# BabyPC.net
KiCad netlist of a schematic drawn in EAGLE
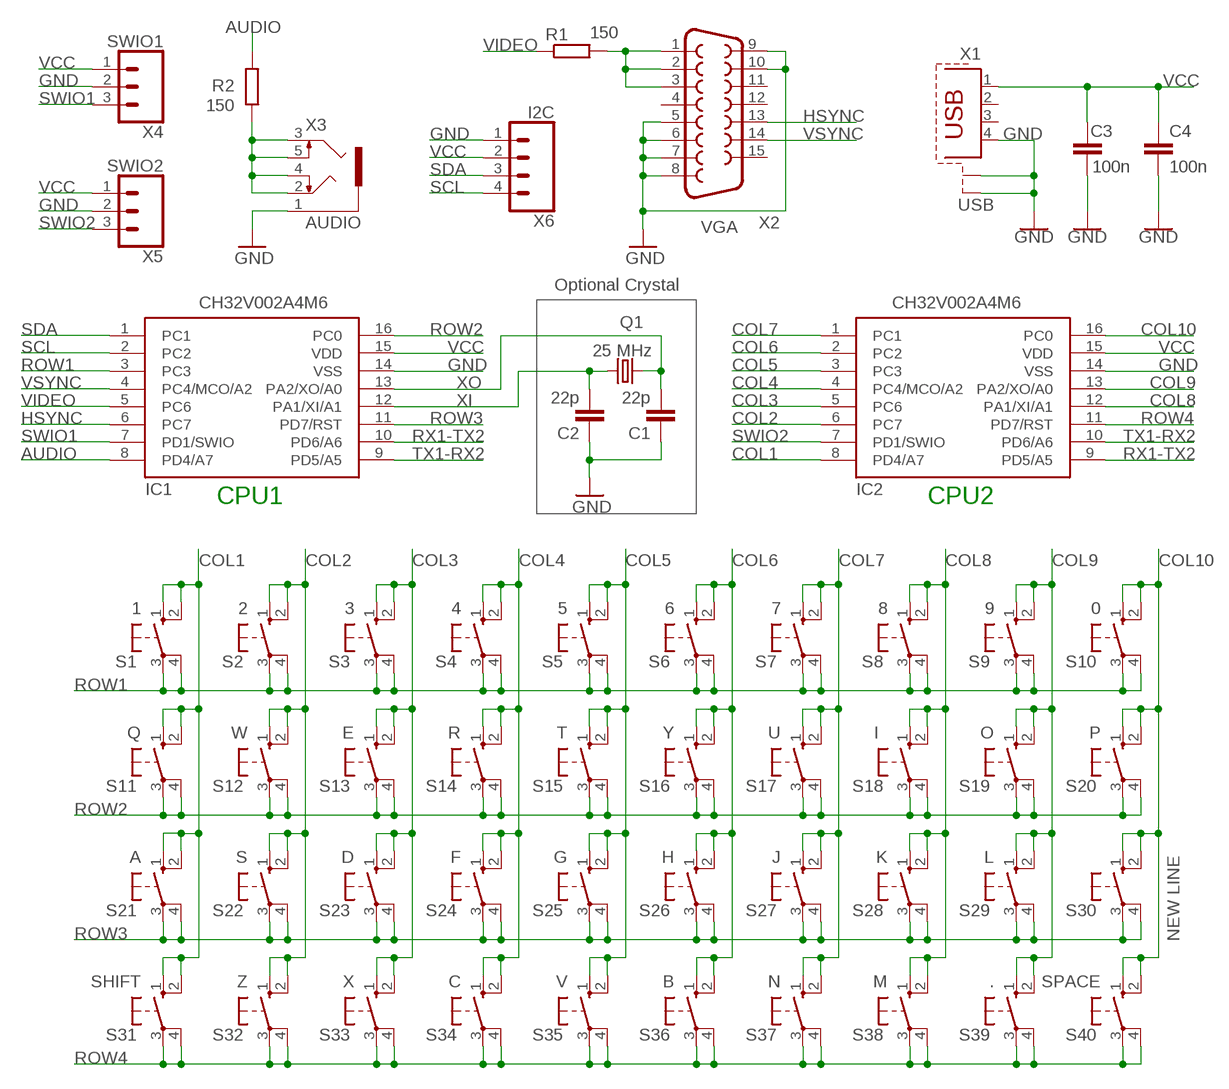
[diagram p0: schematic, sheet 1]

(export (version "E")
  (design (tool "Eeschema 10.0.6"))
  (components
    (comp (ref "C1")
      (value "22p")
      (footprint "eagle-import:C050-024X044")
      (libsource (lib "eagle-import") (part "C-EU050-024X044"))
    )
    (comp (ref "C2")
      (value "22p")
      (footprint "eagle-import:C050-024X044")
      (libsource (lib "eagle-import") (part "C-EU050-024X044"))
    )
    (comp (ref "C3")
      (value "100n")
      (footprint "eagle-import:C050-024X044")
      (libsource (lib "eagle-import") (part "C-EU050-024X044"))
    )
    (comp (ref "C4")
      (value "100n")
      (footprint "eagle-import:C050-024X044")
      (libsource (lib "eagle-import") (part "C-EU050-024X044"))
    )
    (comp (ref "IC1")
      (value "CH32V002A4M6")
      (footprint "eagle-import:SOP16")
      (libsource (lib "eagle-import") (part "CH32V002A4M6"))
    )
    (comp (ref "IC2")
      (value "CH32V002A4M6")
      (footprint "eagle-import:SOP16")
      (libsource (lib "eagle-import") (part "CH32V002A4M6"))
    )
    (comp (ref "Q1")
      (value "25 MHz")
      (footprint "eagle-import:HC49U-V")
      (libsource (lib "eagle-import") (part "CRYSTALHC49U-V"))
    )
    (comp (ref "R1")
      (value "150")
      (footprint "eagle-import:0204_7")
      (libsource (lib "eagle-import") (part "R-EU_0204/7"))
    )
    (comp (ref "R2")
      (value "150")
      (footprint "eagle-import:0204_7")
      (libsource (lib "eagle-import") (part "R-EU_0204/7"))
    )
    (comp (ref "S1")
      (value "1")
      (footprint "eagle-import:B3F-10XX")
      (fields (field (name "MPN") "B3F-1000"))
      (libsource (lib "eagle-import") (part "10-XX"))
    )
    (comp (ref "S2")
      (value "2")
      (footprint "eagle-import:B3F-10XX")
      (fields (field (name "MPN") "B3F-1000"))
      (libsource (lib "eagle-import") (part "10-XX"))
    )
    (comp (ref "S3")
      (value "3")
      (footprint "eagle-import:B3F-10XX")
      (fields (field (name "MPN") "B3F-1000"))
      (libsource (lib "eagle-import") (part "10-XX"))
    )
    (comp (ref "S4")
      (value "4")
      (footprint "eagle-import:B3F-10XX")
      (fields (field (name "MPN") "B3F-1000"))
      (libsource (lib "eagle-import") (part "10-XX"))
    )
    (comp (ref "S5")
      (value "5")
      (footprint "eagle-import:B3F-10XX")
      (fields (field (name "MPN") "B3F-1000"))
      (libsource (lib "eagle-import") (part "10-XX"))
    )
    (comp (ref "S6")
      (value "6")
      (footprint "eagle-import:B3F-10XX")
      (fields (field (name "MPN") "B3F-1000"))
      (libsource (lib "eagle-import") (part "10-XX"))
    )
    (comp (ref "S7")
      (value "7")
      (footprint "eagle-import:B3F-10XX")
      (fields (field (name "MPN") "B3F-1000"))
      (libsource (lib "eagle-import") (part "10-XX"))
    )
    (comp (ref "S8")
      (value "8")
      (footprint "eagle-import:B3F-10XX")
      (fields (field (name "MPN") "B3F-1000"))
      (libsource (lib "eagle-import") (part "10-XX"))
    )
    (comp (ref "S9")
      (value "9")
      (footprint "eagle-import:B3F-10XX")
      (fields (field (name "MPN") "B3F-1000"))
      (libsource (lib "eagle-import") (part "10-XX"))
    )
    (comp (ref "S10")
      (value "0")
      (footprint "eagle-import:B3F-10XX")
      (fields (field (name "MPN") "B3F-1000"))
      (libsource (lib "eagle-import") (part "10-XX"))
    )
    (comp (ref "S11")
      (value "Q")
      (footprint "eagle-import:B3F-10XX")
      (fields (field (name "MPN") "B3F-1000"))
      (libsource (lib "eagle-import") (part "10-XX"))
    )
    (comp (ref "S12")
      (value "W")
      (footprint "eagle-import:B3F-10XX")
      (fields (field (name "MPN") "B3F-1000"))
      (libsource (lib "eagle-import") (part "10-XX"))
    )
    (comp (ref "S13")
      (value "E")
      (footprint "eagle-import:B3F-10XX")
      (fields (field (name "MPN") "B3F-1000"))
      (libsource (lib "eagle-import") (part "10-XX"))
    )
    (comp (ref "S14")
      (value "R")
      (footprint "eagle-import:B3F-10XX")
      (fields (field (name "MPN") "B3F-1000"))
      (libsource (lib "eagle-import") (part "10-XX"))
    )
    (comp (ref "S15")
      (value "T")
      (footprint "eagle-import:B3F-10XX")
      (fields (field (name "MPN") "B3F-1000"))
      (libsource (lib "eagle-import") (part "10-XX"))
    )
    (comp (ref "S16")
      (value "Y")
      (footprint "eagle-import:B3F-10XX")
      (fields (field (name "MPN") "B3F-1000"))
      (libsource (lib "eagle-import") (part "10-XX"))
    )
    (comp (ref "S17")
      (value "U")
      (footprint "eagle-import:B3F-10XX")
      (fields (field (name "MPN") "B3F-1000"))
      (libsource (lib "eagle-import") (part "10-XX"))
    )
    (comp (ref "S18")
      (value "I")
      (footprint "eagle-import:B3F-10XX")
      (fields (field (name "MPN") "B3F-1000"))
      (libsource (lib "eagle-import") (part "10-XX"))
    )
    (comp (ref "S19")
      (value "O")
      (footprint "eagle-import:B3F-10XX")
      (fields (field (name "MPN") "B3F-1000"))
      (libsource (lib "eagle-import") (part "10-XX"))
    )
    (comp (ref "S20")
      (value "P")
      (footprint "eagle-import:B3F-10XX")
      (fields (field (name "MPN") "B3F-1000"))
      (libsource (lib "eagle-import") (part "10-XX"))
    )
    (comp (ref "S21")
      (value "A")
      (footprint "eagle-import:B3F-10XX")
      (fields (field (name "MPN") "B3F-1000"))
      (libsource (lib "eagle-import") (part "10-XX"))
    )
    (comp (ref "S22")
      (value "S")
      (footprint "eagle-import:B3F-10XX")
      (fields (field (name "MPN") "B3F-1000"))
      (libsource (lib "eagle-import") (part "10-XX"))
    )
    (comp (ref "S23")
      (value "D")
      (footprint "eagle-import:B3F-10XX")
      (fields (field (name "MPN") "B3F-1000"))
      (libsource (lib "eagle-import") (part "10-XX"))
    )
    (comp (ref "S24")
      (value "F")
      (footprint "eagle-import:B3F-10XX")
      (fields (field (name "MPN") "B3F-1000"))
      (libsource (lib "eagle-import") (part "10-XX"))
    )
    (comp (ref "S25")
      (value "G")
      (footprint "eagle-import:B3F-10XX")
      (fields (field (name "MPN") "B3F-1000"))
      (libsource (lib "eagle-import") (part "10-XX"))
    )
    (comp (ref "S26")
      (value "H")
      (footprint "eagle-import:B3F-10XX")
      (fields (field (name "MPN") "B3F-1000"))
      (libsource (lib "eagle-import") (part "10-XX"))
    )
    (comp (ref "S27")
      (value "J")
      (footprint "eagle-import:B3F-10XX")
      (fields (field (name "MPN") "B3F-1000"))
      (libsource (lib "eagle-import") (part "10-XX"))
    )
    (comp (ref "S28")
      (value "K")
      (footprint "eagle-import:B3F-10XX")
      (fields (field (name "MPN") "B3F-1000"))
      (libsource (lib "eagle-import") (part "10-XX"))
    )
    (comp (ref "S29")
      (value "L")
      (footprint "eagle-import:B3F-10XX")
      (fields (field (name "MPN") "B3F-1000"))
      (libsource (lib "eagle-import") (part "10-XX"))
    )
    (comp (ref "S30")
      (value "NEW LINE")
      (footprint "eagle-import:B3F-10XX")
      (fields (field (name "MPN") "B3F-1000"))
      (libsource (lib "eagle-import") (part "10-XX"))
    )
    (comp (ref "S31")
      (value "SHIFT")
      (footprint "eagle-import:B3F-10XX")
      (fields (field (name "MPN") "B3F-1000"))
      (libsource (lib "eagle-import") (part "10-XX"))
    )
    (comp (ref "S32")
      (value "Z")
      (footprint "eagle-import:B3F-10XX")
      (fields (field (name "MPN") "B3F-1000"))
      (libsource (lib "eagle-import") (part "10-XX"))
    )
    (comp (ref "S33")
      (value "X")
      (footprint "eagle-import:B3F-10XX")
      (fields (field (name "MPN") "B3F-1000"))
      (libsource (lib "eagle-import") (part "10-XX"))
    )
    (comp (ref "S34")
      (value "C")
      (footprint "eagle-import:B3F-10XX")
      (fields (field (name "MPN") "B3F-1000"))
      (libsource (lib "eagle-import") (part "10-XX"))
    )
    (comp (ref "S35")
      (value "V")
      (footprint "eagle-import:B3F-10XX")
      (fields (field (name "MPN") "B3F-1000"))
      (libsource (lib "eagle-import") (part "10-XX"))
    )
    (comp (ref "S36")
      (value "B")
      (footprint "eagle-import:B3F-10XX")
      (fields (field (name "MPN") "B3F-1000"))
      (libsource (lib "eagle-import") (part "10-XX"))
    )
    (comp (ref "S37")
      (value "N")
      (footprint "eagle-import:B3F-10XX")
      (fields (field (name "MPN") "B3F-1000"))
      (libsource (lib "eagle-import") (part "10-XX"))
    )
    (comp (ref "S38")
      (value "M")
      (footprint "eagle-import:B3F-10XX")
      (fields (field (name "MPN") "B3F-1000"))
      (libsource (lib "eagle-import") (part "10-XX"))
    )
    (comp (ref "S39")
      (value ".")
      (footprint "eagle-import:B3F-10XX")
      (fields (field (name "MPN") "B3F-1000"))
      (libsource (lib "eagle-import") (part "10-XX"))
    )
    (comp (ref "S40")
      (value "SPACE")
      (footprint "eagle-import:B3F-10XX")
      (fields (field (name "MPN") "B3F-1000"))
      (libsource (lib "eagle-import") (part "10-XX"))
    )
    (comp (ref "X1")
      (value "USB")
      (footprint "eagle-import:PN61729-S")
      (libsource (lib "eagle-import") (part "PN61729-S"))
    )
    (comp (ref "X2")
      (value "VGA")
      (footprint "eagle-import:HDF15H")
      (libsource (lib "eagle-import") (part "F15HDH"))
    )
    (comp (ref "X3")
      (value "AUDIO")
      (footprint "eagle-import:1503_09")
      (libsource (lib "eagle-import") (part "1503_09"))
    )
    (comp (ref "X4")
      (value "SWIO1")
      (footprint "eagle-import:1X03_LONGPADS")
      (libsource (lib "eagle-import") (part "CONN_03LONGPADS"))
    )
    (comp (ref "X5")
      (value "SWIO2")
      (footprint "eagle-import:1X03_LONGPADS")
      (libsource (lib "eagle-import") (part "CONN_03LONGPADS"))
    )
    (comp (ref "X6")
      (value "I2C")
      (footprint "eagle-import:1X04_LONGPADS")
      (libsource (lib "eagle-import") (part "CONN_04LONGPADS"))
    )
  )
  (nets
    (net (code "1") (name "/AUDIO") (class "Default")
      (node (ref "IC1") (pin "8") (pinfunction "PD4/A7_8") (pintype "bidirectional"))
      (node (ref "R2") (pin "2") (pinfunction "2_2") (pintype "passive"))
    )
    (net (code "2") (name "/COL1") (class "Default")
      (node (ref "IC2") (pin "8") (pinfunction "PD4/A7_8") (pintype "bidirectional"))
      (node (ref "S1") (pin "1") (pinfunction "S_1") (pintype "passive"))
      (node (ref "S1") (pin "2") (pinfunction "S1_2") (pintype "passive"))
      (node (ref "S11") (pin "1") (pinfunction "S_1") (pintype "passive"))
      (node (ref "S11") (pin "2") (pinfunction "S1_2") (pintype "passive"))
      (node (ref "S21") (pin "1") (pinfunction "S_1") (pintype "passive"))
      (node (ref "S21") (pin "2") (pinfunction "S1_2") (pintype "passive"))
      (node (ref "S31") (pin "1") (pinfunction "S_1") (pintype "passive"))
      (node (ref "S31") (pin "2") (pinfunction "S1_2") (pintype "passive"))
    )
    (net (code "3") (name "/COL2") (class "Default")
      (node (ref "IC2") (pin "6") (pinfunction "PC7_6") (pintype "bidirectional"))
      (node (ref "S12") (pin "1") (pinfunction "S_1") (pintype "passive"))
      (node (ref "S12") (pin "2") (pinfunction "S1_2") (pintype "passive"))
      (node (ref "S2") (pin "1") (pinfunction "S_1") (pintype "passive"))
      (node (ref "S2") (pin "2") (pinfunction "S1_2") (pintype "passive"))
      (node (ref "S22") (pin "1") (pinfunction "S_1") (pintype "passive"))
      (node (ref "S22") (pin "2") (pinfunction "S1_2") (pintype "passive"))
      (node (ref "S32") (pin "1") (pinfunction "S_1") (pintype "passive"))
      (node (ref "S32") (pin "2") (pinfunction "S1_2") (pintype "passive"))
    )
    (net (code "4") (name "/COL3") (class "Default")
      (node (ref "IC2") (pin "5") (pinfunction "PC6_5") (pintype "bidirectional"))
      (node (ref "S13") (pin "1") (pinfunction "S_1") (pintype "passive"))
      (node (ref "S13") (pin "2") (pinfunction "S1_2") (pintype "passive"))
      (node (ref "S23") (pin "1") (pinfunction "S_1") (pintype "passive"))
      (node (ref "S23") (pin "2") (pinfunction "S1_2") (pintype "passive"))
      (node (ref "S3") (pin "1") (pinfunction "S_1") (pintype "passive"))
      (node (ref "S3") (pin "2") (pinfunction "S1_2") (pintype "passive"))
      (node (ref "S33") (pin "1") (pinfunction "S_1") (pintype "passive"))
      (node (ref "S33") (pin "2") (pinfunction "S1_2") (pintype "passive"))
    )
    (net (code "5") (name "/COL4") (class "Default")
      (node (ref "IC2") (pin "4") (pinfunction "PC4/MCO/A2_4") (pintype "bidirectional"))
      (node (ref "S14") (pin "1") (pinfunction "S_1") (pintype "passive"))
      (node (ref "S14") (pin "2") (pinfunction "S1_2") (pintype "passive"))
      (node (ref "S24") (pin "1") (pinfunction "S_1") (pintype "passive"))
      (node (ref "S24") (pin "2") (pinfunction "S1_2") (pintype "passive"))
      (node (ref "S34") (pin "1") (pinfunction "S_1") (pintype "passive"))
      (node (ref "S34") (pin "2") (pinfunction "S1_2") (pintype "passive"))
      (node (ref "S4") (pin "1") (pinfunction "S_1") (pintype "passive"))
      (node (ref "S4") (pin "2") (pinfunction "S1_2") (pintype "passive"))
    )
    (net (code "6") (name "/COL5") (class "Default")
      (node (ref "IC2") (pin "3") (pinfunction "PC3_3") (pintype "bidirectional"))
      (node (ref "S15") (pin "1") (pinfunction "S_1") (pintype "passive"))
      (node (ref "S15") (pin "2") (pinfunction "S1_2") (pintype "passive"))
      (node (ref "S25") (pin "1") (pinfunction "S_1") (pintype "passive"))
      (node (ref "S25") (pin "2") (pinfunction "S1_2") (pintype "passive"))
      (node (ref "S35") (pin "1") (pinfunction "S_1") (pintype "passive"))
      (node (ref "S35") (pin "2") (pinfunction "S1_2") (pintype "passive"))
      (node (ref "S5") (pin "1") (pinfunction "S_1") (pintype "passive"))
      (node (ref "S5") (pin "2") (pinfunction "S1_2") (pintype "passive"))
    )
    (net (code "7") (name "/COL6") (class "Default")
      (node (ref "IC2") (pin "2") (pinfunction "PC2_2") (pintype "bidirectional"))
      (node (ref "S16") (pin "1") (pinfunction "S_1") (pintype "passive"))
      (node (ref "S16") (pin "2") (pinfunction "S1_2") (pintype "passive"))
      (node (ref "S26") (pin "1") (pinfunction "S_1") (pintype "passive"))
      (node (ref "S26") (pin "2") (pinfunction "S1_2") (pintype "passive"))
      (node (ref "S36") (pin "1") (pinfunction "S_1") (pintype "passive"))
      (node (ref "S36") (pin "2") (pinfunction "S1_2") (pintype "passive"))
      (node (ref "S6") (pin "1") (pinfunction "S_1") (pintype "passive"))
      (node (ref "S6") (pin "2") (pinfunction "S1_2") (pintype "passive"))
    )
    (net (code "8") (name "/COL7") (class "Default")
      (node (ref "IC2") (pin "1") (pinfunction "PC1_1") (pintype "bidirectional"))
      (node (ref "S17") (pin "1") (pinfunction "S_1") (pintype "passive"))
      (node (ref "S17") (pin "2") (pinfunction "S1_2") (pintype "passive"))
      (node (ref "S27") (pin "1") (pinfunction "S_1") (pintype "passive"))
      (node (ref "S27") (pin "2") (pinfunction "S1_2") (pintype "passive"))
      (node (ref "S37") (pin "1") (pinfunction "S_1") (pintype "passive"))
      (node (ref "S37") (pin "2") (pinfunction "S1_2") (pintype "passive"))
      (node (ref "S7") (pin "1") (pinfunction "S_1") (pintype "passive"))
      (node (ref "S7") (pin "2") (pinfunction "S1_2") (pintype "passive"))
    )
    (net (code "9") (name "/COL8") (class "Default")
      (node (ref "IC2") (pin "12") (pinfunction "PA1/XI/A1_12") (pintype "bidirectional"))
      (node (ref "S18") (pin "1") (pinfunction "S_1") (pintype "passive"))
      (node (ref "S18") (pin "2") (pinfunction "S1_2") (pintype "passive"))
      (node (ref "S28") (pin "1") (pinfunction "S_1") (pintype "passive"))
      (node (ref "S28") (pin "2") (pinfunction "S1_2") (pintype "passive"))
      (node (ref "S38") (pin "1") (pinfunction "S_1") (pintype "passive"))
      (node (ref "S38") (pin "2") (pinfunction "S1_2") (pintype "passive"))
      (node (ref "S8") (pin "1") (pinfunction "S_1") (pintype "passive"))
      (node (ref "S8") (pin "2") (pinfunction "S1_2") (pintype "passive"))
    )
    (net (code "10") (name "/COL9") (class "Default")
      (node (ref "IC2") (pin "13") (pinfunction "PA2/XO/A0_13") (pintype "bidirectional"))
      (node (ref "S19") (pin "1") (pinfunction "S_1") (pintype "passive"))
      (node (ref "S19") (pin "2") (pinfunction "S1_2") (pintype "passive"))
      (node (ref "S29") (pin "1") (pinfunction "S_1") (pintype "passive"))
      (node (ref "S29") (pin "2") (pinfunction "S1_2") (pintype "passive"))
      (node (ref "S39") (pin "1") (pinfunction "S_1") (pintype "passive"))
      (node (ref "S39") (pin "2") (pinfunction "S1_2") (pintype "passive"))
      (node (ref "S9") (pin "1") (pinfunction "S_1") (pintype "passive"))
      (node (ref "S9") (pin "2") (pinfunction "S1_2") (pintype "passive"))
    )
    (net (code "11") (name "/COL10") (class "Default")
      (node (ref "IC2") (pin "16") (pinfunction "PC0_16") (pintype "bidirectional"))
      (node (ref "S10") (pin "1") (pinfunction "S_1") (pintype "passive"))
      (node (ref "S10") (pin "2") (pinfunction "S1_2") (pintype "passive"))
      (node (ref "S20") (pin "1") (pinfunction "S_1") (pintype "passive"))
      (node (ref "S20") (pin "2") (pinfunction "S1_2") (pintype "passive"))
      (node (ref "S30") (pin "1") (pinfunction "S_1") (pintype "passive"))
      (node (ref "S30") (pin "2") (pinfunction "S1_2") (pintype "passive"))
      (node (ref "S40") (pin "1") (pinfunction "S_1") (pintype "passive"))
      (node (ref "S40") (pin "2") (pinfunction "S1_2") (pintype "passive"))
    )
    (net (code "12") (name "/HSYNC") (class "Default")
      (node (ref "IC1") (pin "6") (pinfunction "PC7_6") (pintype "bidirectional"))
      (node (ref "X2") (pin "13") (pinfunction "13_13") (pintype "passive"))
    )
    (net (code "13") (name "/ROW1") (class "Default")
      (node (ref "IC1") (pin "3") (pinfunction "PC3_3") (pintype "bidirectional"))
      (node (ref "S1") (pin "3") (pinfunction "P_3") (pintype "passive"))
      (node (ref "S1") (pin "4") (pinfunction "P1_4") (pintype "passive"))
      (node (ref "S10") (pin "3") (pinfunction "P_3") (pintype "passive"))
      (node (ref "S10") (pin "4") (pinfunction "P1_4") (pintype "passive"))
      (node (ref "S2") (pin "3") (pinfunction "P_3") (pintype "passive"))
      (node (ref "S2") (pin "4") (pinfunction "P1_4") (pintype "passive"))
      (node (ref "S3") (pin "3") (pinfunction "P_3") (pintype "passive"))
      (node (ref "S3") (pin "4") (pinfunction "P1_4") (pintype "passive"))
      (node (ref "S4") (pin "3") (pinfunction "P_3") (pintype "passive"))
      (node (ref "S4") (pin "4") (pinfunction "P1_4") (pintype "passive"))
      (node (ref "S5") (pin "3") (pinfunction "P_3") (pintype "passive"))
      (node (ref "S5") (pin "4") (pinfunction "P1_4") (pintype "passive"))
      (node (ref "S6") (pin "3") (pinfunction "P_3") (pintype "passive"))
      (node (ref "S6") (pin "4") (pinfunction "P1_4") (pintype "passive"))
      (node (ref "S7") (pin "3") (pinfunction "P_3") (pintype "passive"))
      (node (ref "S7") (pin "4") (pinfunction "P1_4") (pintype "passive"))
      (node (ref "S8") (pin "3") (pinfunction "P_3") (pintype "passive"))
      (node (ref "S8") (pin "4") (pinfunction "P1_4") (pintype "passive"))
      (node (ref "S9") (pin "3") (pinfunction "P_3") (pintype "passive"))
      (node (ref "S9") (pin "4") (pinfunction "P1_4") (pintype "passive"))
    )
    (net (code "14") (name "/ROW2") (class "Default")
      (node (ref "IC1") (pin "16") (pinfunction "PC0_16") (pintype "bidirectional"))
      (node (ref "S11") (pin "3") (pinfunction "P_3") (pintype "passive"))
      (node (ref "S11") (pin "4") (pinfunction "P1_4") (pintype "passive"))
      (node (ref "S12") (pin "3") (pinfunction "P_3") (pintype "passive"))
      (node (ref "S12") (pin "4") (pinfunction "P1_4") (pintype "passive"))
      (node (ref "S13") (pin "3") (pinfunction "P_3") (pintype "passive"))
      (node (ref "S13") (pin "4") (pinfunction "P1_4") (pintype "passive"))
      (node (ref "S14") (pin "3") (pinfunction "P_3") (pintype "passive"))
      (node (ref "S14") (pin "4") (pinfunction "P1_4") (pintype "passive"))
      (node (ref "S15") (pin "3") (pinfunction "P_3") (pintype "passive"))
      (node (ref "S15") (pin "4") (pinfunction "P1_4") (pintype "passive"))
      (node (ref "S16") (pin "3") (pinfunction "P_3") (pintype "passive"))
      (node (ref "S16") (pin "4") (pinfunction "P1_4") (pintype "passive"))
      (node (ref "S17") (pin "3") (pinfunction "P_3") (pintype "passive"))
      (node (ref "S17") (pin "4") (pinfunction "P1_4") (pintype "passive"))
      (node (ref "S18") (pin "3") (pinfunction "P_3") (pintype "passive"))
      (node (ref "S18") (pin "4") (pinfunction "P1_4") (pintype "passive"))
      (node (ref "S19") (pin "3") (pinfunction "P_3") (pintype "passive"))
      (node (ref "S19") (pin "4") (pinfunction "P1_4") (pintype "passive"))
      (node (ref "S20") (pin "3") (pinfunction "P_3") (pintype "passive"))
      (node (ref "S20") (pin "4") (pinfunction "P1_4") (pintype "passive"))
    )
    (net (code "15") (name "/ROW3") (class "Default")
      (node (ref "IC1") (pin "11") (pinfunction "PD7/RST_11") (pintype "bidirectional"))
      (node (ref "S21") (pin "3") (pinfunction "P_3") (pintype "passive"))
      (node (ref "S21") (pin "4") (pinfunction "P1_4") (pintype "passive"))
      (node (ref "S22") (pin "3") (pinfunction "P_3") (pintype "passive"))
      (node (ref "S22") (pin "4") (pinfunction "P1_4") (pintype "passive"))
      (node (ref "S23") (pin "3") (pinfunction "P_3") (pintype "passive"))
      (node (ref "S23") (pin "4") (pinfunction "P1_4") (pintype "passive"))
      (node (ref "S24") (pin "3") (pinfunction "P_3") (pintype "passive"))
      (node (ref "S24") (pin "4") (pinfunction "P1_4") (pintype "passive"))
      (node (ref "S25") (pin "3") (pinfunction "P_3") (pintype "passive"))
      (node (ref "S25") (pin "4") (pinfunction "P1_4") (pintype "passive"))
      (node (ref "S26") (pin "3") (pinfunction "P_3") (pintype "passive"))
      (node (ref "S26") (pin "4") (pinfunction "P1_4") (pintype "passive"))
      (node (ref "S27") (pin "3") (pinfunction "P_3") (pintype "passive"))
      (node (ref "S27") (pin "4") (pinfunction "P1_4") (pintype "passive"))
      (node (ref "S28") (pin "3") (pinfunction "P_3") (pintype "passive"))
      (node (ref "S28") (pin "4") (pinfunction "P1_4") (pintype "passive"))
      (node (ref "S29") (pin "3") (pinfunction "P_3") (pintype "passive"))
      (node (ref "S29") (pin "4") (pinfunction "P1_4") (pintype "passive"))
      (node (ref "S30") (pin "3") (pinfunction "P_3") (pintype "passive"))
      (node (ref "S30") (pin "4") (pinfunction "P1_4") (pintype "passive"))
    )
    (net (code "16") (name "/ROW4") (class "Default")
      (node (ref "IC2") (pin "11") (pinfunction "PD7/RST_11") (pintype "bidirectional"))
      (node (ref "S31") (pin "3") (pinfunction "P_3") (pintype "passive"))
      (node (ref "S31") (pin "4") (pinfunction "P1_4") (pintype "passive"))
      (node (ref "S32") (pin "3") (pinfunction "P_3") (pintype "passive"))
      (node (ref "S32") (pin "4") (pinfunction "P1_4") (pintype "passive"))
      (node (ref "S33") (pin "3") (pinfunction "P_3") (pintype "passive"))
      (node (ref "S33") (pin "4") (pinfunction "P1_4") (pintype "passive"))
      (node (ref "S34") (pin "3") (pinfunction "P_3") (pintype "passive"))
      (node (ref "S34") (pin "4") (pinfunction "P1_4") (pintype "passive"))
      (node (ref "S35") (pin "3") (pinfunction "P_3") (pintype "passive"))
      (node (ref "S35") (pin "4") (pinfunction "P1_4") (pintype "passive"))
      (node (ref "S36") (pin "3") (pinfunction "P_3") (pintype "passive"))
      (node (ref "S36") (pin "4") (pinfunction "P1_4") (pintype "passive"))
      (node (ref "S37") (pin "3") (pinfunction "P_3") (pintype "passive"))
      (node (ref "S37") (pin "4") (pinfunction "P1_4") (pintype "passive"))
      (node (ref "S38") (pin "3") (pinfunction "P_3") (pintype "passive"))
      (node (ref "S38") (pin "4") (pinfunction "P1_4") (pintype "passive"))
      (node (ref "S39") (pin "3") (pinfunction "P_3") (pintype "passive"))
      (node (ref "S39") (pin "4") (pinfunction "P1_4") (pintype "passive"))
      (node (ref "S40") (pin "3") (pinfunction "P_3") (pintype "passive"))
      (node (ref "S40") (pin "4") (pinfunction "P1_4") (pintype "passive"))
    )
    (net (code "17") (name "/RX1-TX2") (class "Default")
      (node (ref "IC1") (pin "10") (pinfunction "PD6/A6_10") (pintype "bidirectional"))
      (node (ref "IC2") (pin "9") (pinfunction "PD5/A5_9") (pintype "bidirectional"))
    )
    (net (code "18") (name "/SCL") (class "Default")
      (node (ref "IC1") (pin "2") (pinfunction "PC2_2") (pintype "bidirectional"))
      (node (ref "X6") (pin "4") (pinfunction "4_4") (pintype "passive"))
    )
    (net (code "19") (name "/SDA") (class "Default")
      (node (ref "IC1") (pin "1") (pinfunction "PC1_1") (pintype "bidirectional"))
      (node (ref "X6") (pin "3") (pinfunction "3_3") (pintype "passive"))
    )
    (net (code "20") (name "/SWIO1") (class "Default")
      (node (ref "IC1") (pin "7") (pinfunction "PD1/SWIO_7") (pintype "bidirectional"))
      (node (ref "X4") (pin "3") (pinfunction "3_3") (pintype "passive"))
    )
    (net (code "21") (name "/SWIO2") (class "Default")
      (node (ref "IC2") (pin "7") (pinfunction "PD1/SWIO_7") (pintype "bidirectional"))
      (node (ref "X5") (pin "3") (pinfunction "3_3") (pintype "passive"))
    )
    (net (code "22") (name "/TX1-RX2") (class "Default")
      (node (ref "IC1") (pin "9") (pinfunction "PD5/A5_9") (pintype "bidirectional"))
      (node (ref "IC2") (pin "10") (pinfunction "PD6/A6_10") (pintype "bidirectional"))
    )
    (net (code "23") (name "/VCC") (class "Default")
      (node (ref "C3") (pin "2") (pinfunction "2_2") (pintype "passive"))
      (node (ref "C4") (pin "1") (pinfunction "1_1") (pintype "passive"))
      (node (ref "IC1") (pin "15") (pinfunction "VDD_15") (pintype "power_in"))
      (node (ref "IC2") (pin "15") (pinfunction "VDD_15") (pintype "power_in"))
      (node (ref "X1") (pin "1") (pinfunction "1_1") (pintype "passive"))
      (node (ref "X4") (pin "1") (pinfunction "1_1") (pintype "passive"))
      (node (ref "X5") (pin "1") (pinfunction "1_1") (pintype "passive"))
      (node (ref "X6") (pin "2") (pinfunction "2_2") (pintype "passive"))
    )
    (net (code "24") (name "/VIDEO") (class "Default")
      (node (ref "IC1") (pin "5") (pinfunction "PC6_5") (pintype "bidirectional"))
      (node (ref "R1") (pin "1") (pinfunction "1_1") (pintype "passive"))
    )
    (net (code "25") (name "/VSYNC") (class "Default")
      (node (ref "IC1") (pin "4") (pinfunction "PC4/MCO/A2_4") (pintype "bidirectional"))
      (node (ref "X2") (pin "14") (pinfunction "14_14") (pintype "passive"))
    )
    (net (code "26") (name "/XI") (class "Default")
      (node (ref "C2") (pin "2") (pinfunction "2_2") (pintype "passive"))
      (node (ref "IC1") (pin "12") (pinfunction "PA1/XI/A1_12") (pintype "bidirectional"))
      (node (ref "Q1") (pin "2") (pinfunction "2_2") (pintype "passive"))
    )
    (net (code "27") (name "/XO") (class "Default")
      (node (ref "C1") (pin "2") (pinfunction "2_2") (pintype "passive"))
      (node (ref "IC1") (pin "13") (pinfunction "PA2/XO/A0_13") (pintype "bidirectional"))
      (node (ref "Q1") (pin "1") (pinfunction "1_1") (pintype "passive"))
    )
    (net (code "28") (name "GND") (class "Default")
      (node (ref "C1") (pin "1") (pinfunction "1_1") (pintype "passive"))
      (node (ref "C2") (pin "1") (pinfunction "1_1") (pintype "passive"))
      (node (ref "C3") (pin "1") (pinfunction "1_1") (pintype "passive"))
      (node (ref "C4") (pin "2") (pinfunction "2_2") (pintype "passive"))
      (node (ref "IC1") (pin "14") (pinfunction "VSS_14") (pintype "power_in"))
      (node (ref "IC2") (pin "14") (pinfunction "VSS_14") (pintype "power_in"))
      (node (ref "X1") (pin "4") (pinfunction "4_4") (pintype "passive"))
      (node (ref "X1") (pin "S1") (pinfunction "S1_S1") (pintype "passive"))
      (node (ref "X1") (pin "S2") (pinfunction "S2_S2") (pintype "passive"))
      (node (ref "X2") (pin "10") (pinfunction "10_10") (pintype "passive"))
      (node (ref "X2") (pin "5") (pinfunction "5_5") (pintype "passive"))
      (node (ref "X2") (pin "6") (pinfunction "6_6") (pintype "passive"))
      (node (ref "X2") (pin "7") (pinfunction "7_7") (pintype "passive"))
      (node (ref "X2") (pin "8") (pinfunction "8_8") (pintype "passive"))
      (node (ref "X2") (pin "9") (pinfunction "9_9") (pintype "passive"))
      (node (ref "X3") (pin "1") (pinfunction "1_1") (pintype "passive"))
      (node (ref "X4") (pin "2") (pinfunction "2_2") (pintype "passive"))
      (node (ref "X5") (pin "2") (pinfunction "2_2") (pintype "passive"))
      (node (ref "X6") (pin "1") (pinfunction "1_1") (pintype "passive"))
    )
    (net (code "29") (name "Net-(R1-Pad2)") (class "Default")
      (node (ref "R1") (pin "2") (pinfunction "2_2") (pintype "passive"))
      (node (ref "X2") (pin "1") (pinfunction "1_1") (pintype "passive"))
      (node (ref "X2") (pin "2") (pinfunction "2_2") (pintype "passive"))
      (node (ref "X2") (pin "3") (pinfunction "3_3") (pintype "passive"))
    )
    (net (code "30") (name "Net-(R2-Pad1)") (class "Default")
      (node (ref "R2") (pin "1") (pinfunction "1_1") (pintype "passive"))
      (node (ref "X3") (pin "2") (pinfunction "2_2") (pintype "passive"))
      (node (ref "X3") (pin "3") (pinfunction "3_3") (pintype "passive"))
      (node (ref "X3") (pin "4") (pinfunction "4_4") (pintype "passive"))
      (node (ref "X3") (pin "5") (pinfunction "5_5") (pintype "passive"))
    )
    (net (code "31") (name "unconnected-(X1-Pad2)") (class "Default")
      (node (ref "X1") (pin "2") (pinfunction "2_2") (pintype "passive"))
    )
    (net (code "32") (name "unconnected-(X1-Pad3)") (class "Default")
      (node (ref "X1") (pin "3") (pinfunction "3_3") (pintype "passive"))
    )
    (net (code "33") (name "unconnected-(X2-Pad4)") (class "Default")
      (node (ref "X2") (pin "4") (pinfunction "4_4") (pintype "passive"))
    )
    (net (code "34") (name "unconnected-(X2-Pad11)") (class "Default")
      (node (ref "X2") (pin "11") (pinfunction "11_11") (pintype "passive"))
    )
    (net (code "35") (name "unconnected-(X2-Pad12)") (class "Default")
      (node (ref "X2") (pin "12") (pinfunction "12_12") (pintype "passive"))
    )
    (net (code "36") (name "unconnected-(X2-Pad15)") (class "Default")
      (node (ref "X2") (pin "15") (pinfunction "15_15") (pintype "passive"))
    )
  )
)
